# V4_0.net
KiCad netlist of a schematic drawn in Altium Designer
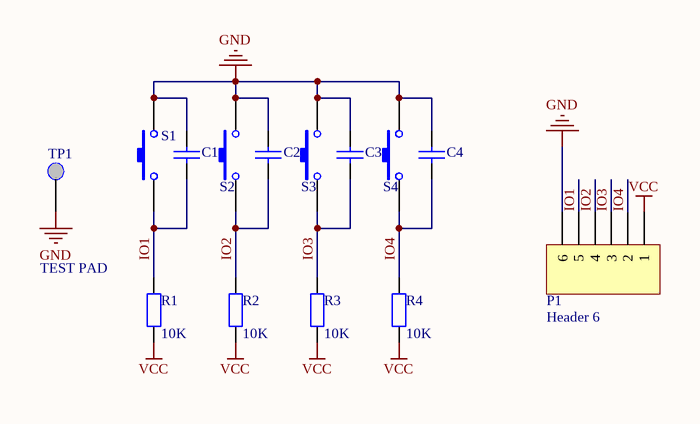
[diagram p0: 起跑突击V4.0.SchDoc]

(export (version "E")
  (design (tool "Eeschema 10.0.6"))
  (components
    (comp (ref "C1")
      (value "Cap")
      (footprint "C2012")
      (description "贴片电容")
      (fields (field (name "PUBLISHER") "Altium Limited"))
      (libsource (lib "Sparks") (part "Cap"))
    )
    (comp (ref "C2")
      (value "Cap")
      (footprint "C2012")
      (description "贴片电容")
      (fields (field (name "PUBLISHER") "Altium Limited"))
      (libsource (lib "Sparks") (part "Cap"))
    )
    (comp (ref "C3")
      (value "Cap")
      (footprint "C2012")
      (description "贴片电容")
      (fields (field (name "PUBLISHER") "Altium Limited"))
      (libsource (lib "Sparks") (part "Cap"))
    )
    (comp (ref "C4")
      (value "Cap")
      (footprint "C2012")
      (description "贴片电容")
      (fields (field (name "PUBLISHER") "Altium Limited"))
      (libsource (lib "Sparks") (part "Cap"))
    )
    (comp (ref "P1")
      (value "Header 6")
      (footprint "HDR1X6")
      (description "Header, 6-Pin")
      (fields (field (name "PUBLISHER") "Altium Limited"))
      (libsource (lib "Sparks") (part "Header 6"))
    )
    (comp (ref "R1")
      (value "10K")
      (footprint "R2012")
      (description "Resistor")
      (fields (field (name "Comment") "Res2") (field (name "PUBLISHER") "Altium Limited"))
      (libsource (lib "Miscellaneous Devices") (part "Res2"))
    )
    (comp (ref "R2")
      (value "10K")
      (footprint "R2012")
      (description "Resistor")
      (fields (field (name "Comment") "Res2") (field (name "PUBLISHER") "Altium Limited"))
      (libsource (lib "Miscellaneous Devices") (part "Res2"))
    )
    (comp (ref "R3")
      (value "10K")
      (footprint "R2012")
      (description "Resistor")
      (fields (field (name "Comment") "Res2") (field (name "PUBLISHER") "Altium Limited"))
      (libsource (lib "Miscellaneous Devices") (part "Res2"))
    )
    (comp (ref "R4")
      (value "10K")
      (footprint "R2012")
      (description "Resistor")
      (fields (field (name "Comment") "Res2") (field (name "PUBLISHER") "Altium Limited"))
      (libsource (lib "Miscellaneous Devices") (part "Res2"))
    )
    (comp (ref "S1")
      (value "SW-PB")
      (footprint "AXIAL-1.0")
      (description "Switch")
      (fields (field (name "PUBLISHER") "Altium Limited"))
      (libsource (lib "Miscellaneous Devices") (part "SW-PB"))
    )
    (comp (ref "S2")
      (value "SW-PB")
      (footprint "AXIAL-1.0")
      (description "Switch")
      (fields (field (name "PUBLISHER") "Altium Limited"))
      (libsource (lib "Miscellaneous Devices") (part "SW-PB"))
    )
    (comp (ref "S3")
      (value "SW-PB")
      (footprint "AXIAL-1.0")
      (description "Switch")
      (fields (field (name "PUBLISHER") "Altium Limited"))
      (libsource (lib "Miscellaneous Devices") (part "SW-PB"))
    )
    (comp (ref "S4")
      (value "SW-PB")
      (footprint "AXIAL-1.0")
      (description "Switch")
      (fields (field (name "PUBLISHER") "Altium Limited"))
      (libsource (lib "Miscellaneous Devices") (part "SW-PB"))
    )
    (comp (ref "TP1") (value "TEST PAD") (footprint "PIN") (libsource (lib "刘爽") (part "TEST PAD")))
  )
  (nets
    (net (code "1") (name "/IO1") (class "Default")
      (node (ref "C1") (pin "1") (pinfunction "1_1") (pintype "passive"))
      (node (ref "P1") (pin "5") (pinfunction "5_5") (pintype "passive"))
      (node (ref "R1") (pin "1") (pinfunction "1_1") (pintype "passive"))
      (node (ref "S1") (pin "1") (pinfunction "1_1") (pintype "passive"))
    )
    (net (code "2") (name "/IO2") (class "Default")
      (node (ref "C2") (pin "1") (pinfunction "1_1") (pintype "passive"))
      (node (ref "P1") (pin "4") (pinfunction "4_4") (pintype "passive"))
      (node (ref "R2") (pin "1") (pinfunction "1_1") (pintype "passive"))
      (node (ref "S2") (pin "1") (pinfunction "1_1") (pintype "passive"))
    )
    (net (code "3") (name "/IO3") (class "Default")
      (node (ref "C3") (pin "1") (pinfunction "1_1") (pintype "passive"))
      (node (ref "P1") (pin "3") (pinfunction "3_3") (pintype "passive"))
      (node (ref "R3") (pin "1") (pinfunction "1_1") (pintype "passive"))
      (node (ref "S3") (pin "1") (pinfunction "1_1") (pintype "passive"))
    )
    (net (code "4") (name "/IO4") (class "Default")
      (node (ref "C4") (pin "1") (pinfunction "1_1") (pintype "passive"))
      (node (ref "P1") (pin "2") (pinfunction "2_2") (pintype "passive"))
      (node (ref "R4") (pin "1") (pinfunction "1_1") (pintype "passive"))
      (node (ref "S4") (pin "1") (pinfunction "1_1") (pintype "passive"))
    )
    (net (code "5") (name "GND") (class "Default")
      (node (ref "C1") (pin "2") (pinfunction "2_2") (pintype "passive"))
      (node (ref "C2") (pin "2") (pinfunction "2_2") (pintype "passive"))
      (node (ref "C3") (pin "2") (pinfunction "2_2") (pintype "passive"))
      (node (ref "C4") (pin "2") (pinfunction "2_2") (pintype "passive"))
      (node (ref "P1") (pin "6") (pinfunction "6_6") (pintype "passive"))
      (node (ref "S1") (pin "2") (pinfunction "2_2") (pintype "passive"))
      (node (ref "S2") (pin "2") (pinfunction "2_2") (pintype "passive"))
      (node (ref "S3") (pin "2") (pinfunction "2_2") (pintype "passive"))
      (node (ref "S4") (pin "2") (pinfunction "2_2") (pintype "passive"))
      (node (ref "TP1") (pin "1") (pinfunction "1_1") (pintype "passive"))
    )
    (net (code "6") (name "VCC") (class "Default")
      (node (ref "P1") (pin "1") (pinfunction "1_1") (pintype "passive"))
      (node (ref "R1") (pin "2") (pinfunction "2_2") (pintype "passive"))
      (node (ref "R2") (pin "2") (pinfunction "2_2") (pintype "passive"))
      (node (ref "R3") (pin "2") (pinfunction "2_2") (pintype "passive"))
      (node (ref "R4") (pin "2") (pinfunction "2_2") (pintype "passive"))
    )
  )
)
